# HB-UNI-Sen-PM_v2p1.net
KiCad netlist of a schematic drawn in EAGLE
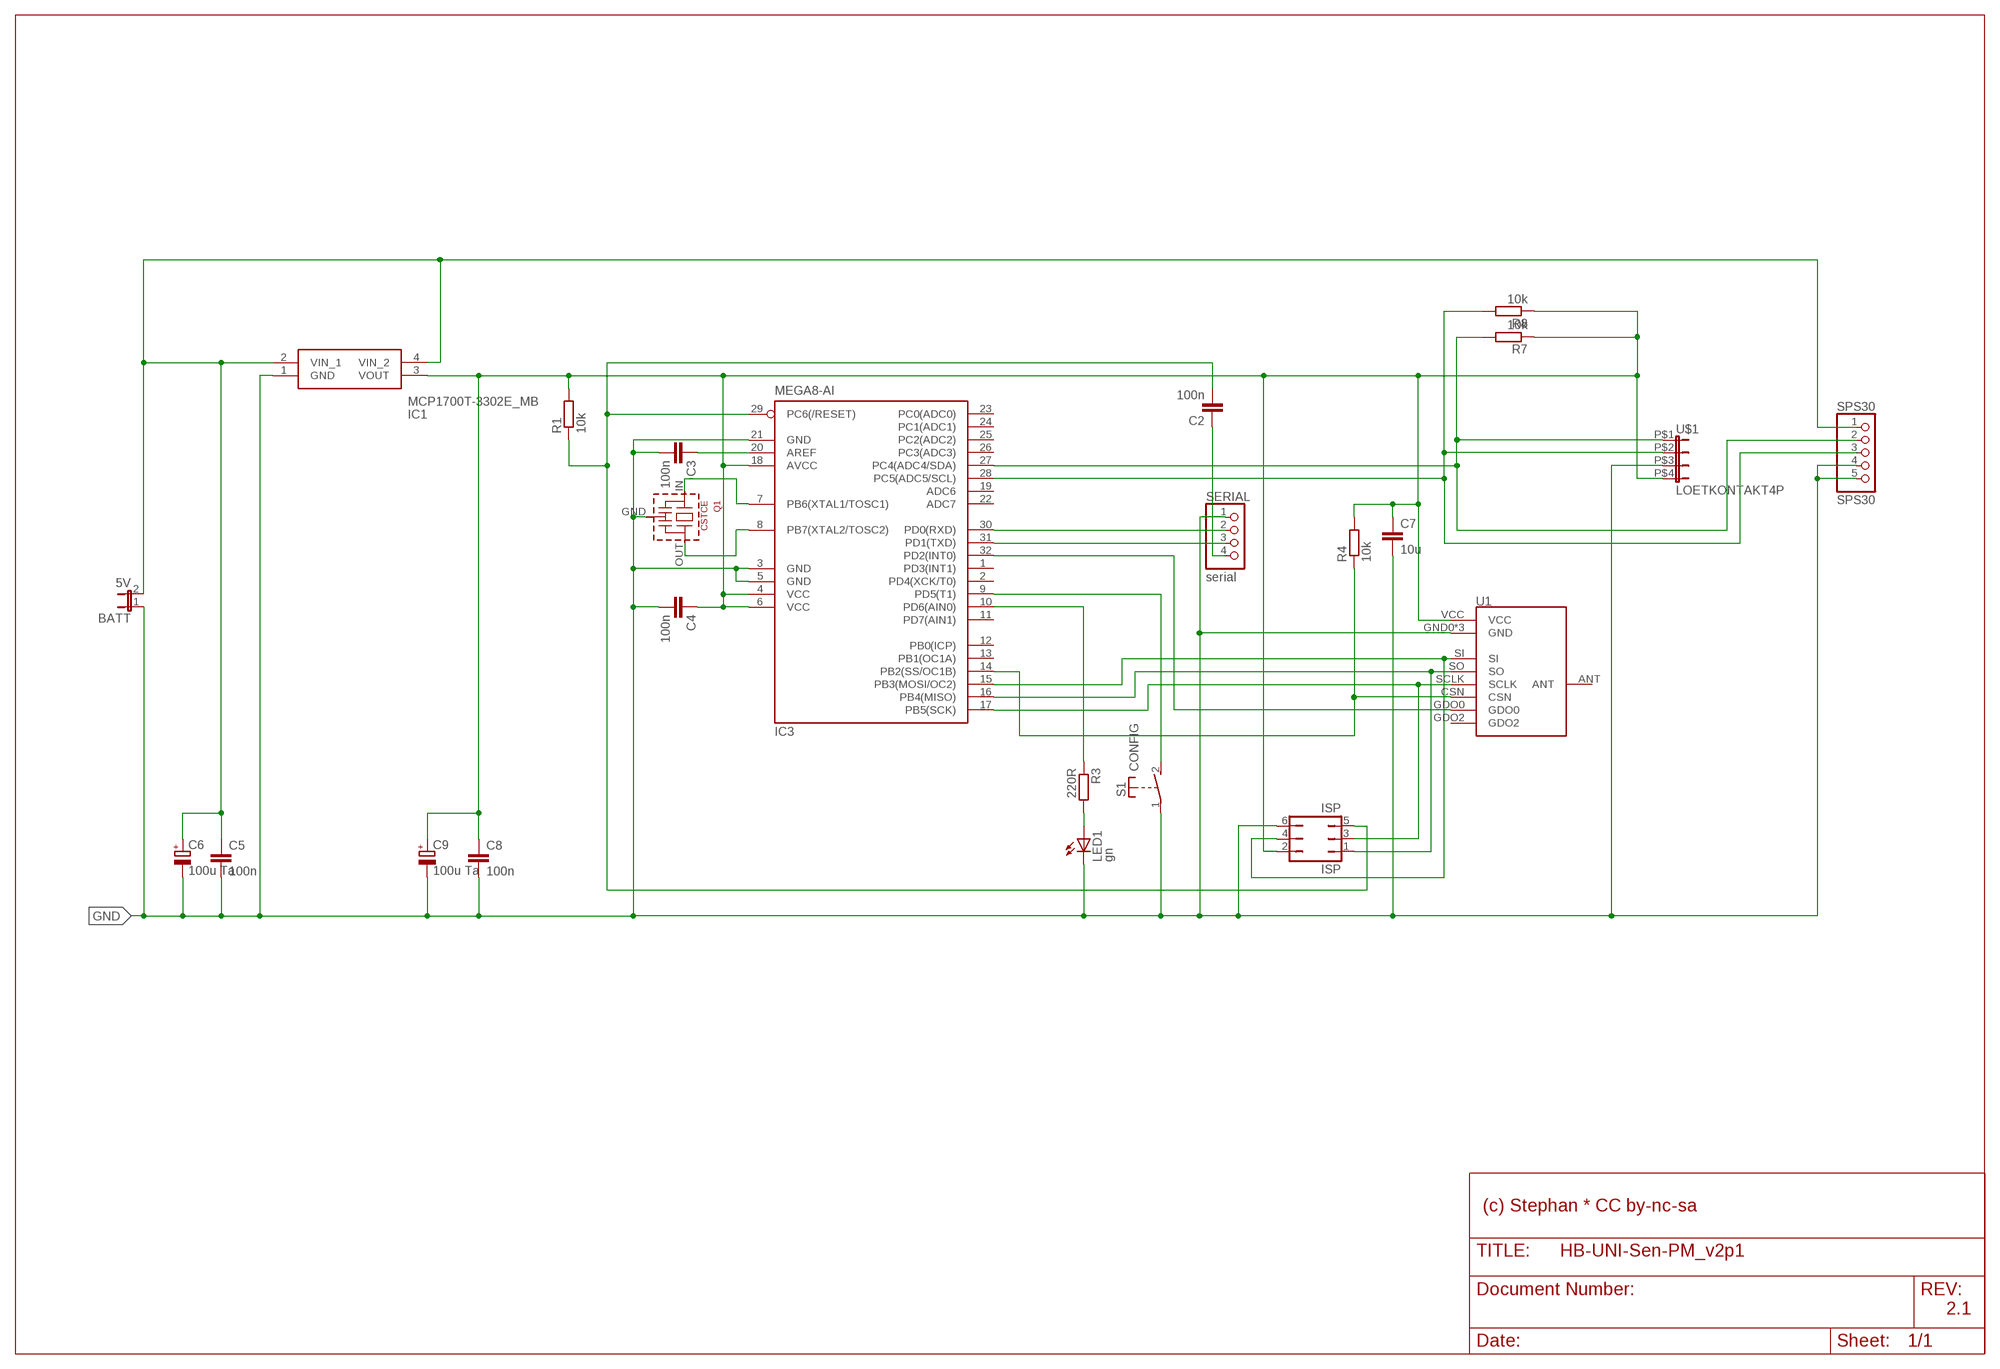
[diagram p0: schematic, sheet 1]

(export (version "E")
  (design (tool "Eeschema 10.0.6"))
  (components
    (comp (ref "BATT")
      (value "5V")
      (footprint "eagle-import:JP1")
      (libsource (lib "eagle-import") (part "JP1E"))
    )
    (comp (ref "C2")
      (value "100n")
      (footprint "eagle-import:C0805K")
      (libsource (lib "eagle-import") (part "C-EUC0805K"))
    )
    (comp (ref "C3")
      (value "100n")
      (footprint "eagle-import:C0805K")
      (libsource (lib "eagle-import") (part "C-EUC0805K"))
    )
    (comp (ref "C4")
      (value "100n")
      (footprint "eagle-import:C0805K")
      (libsource (lib "eagle-import") (part "C-EUC0805K"))
    )
    (comp (ref "C5")
      (value "100n")
      (footprint "eagle-import:C0805K")
      (libsource (lib "eagle-import") (part "C-EUC0805K"))
    )
    (comp (ref "C6")
      (value "100u Ta")
      (footprint "eagle-import:SANYO-OSCON_SMD_C6")
      (libsource (lib "eagle-import") (part "CPOL-EUSANYO_SMD_C6"))
    )
    (comp (ref "C7")
      (value "10u")
      (footprint "eagle-import:C0805K")
      (libsource (lib "eagle-import") (part "C-EUC0805K"))
    )
    (comp (ref "C8")
      (value "100n")
      (footprint "eagle-import:C0805K")
      (libsource (lib "eagle-import") (part "C-EUC0805K"))
    )
    (comp (ref "C9")
      (value "100u Ta")
      (footprint "eagle-import:SANYO-OSCON_SMD_C6")
      (libsource (lib "eagle-import") (part "CPOL-EUSANYO_SMD_C6"))
    )
    (comp (ref "IC1")
      (value "MCP1700T-3302E_MB")
      (footprint "eagle-import:MCP1700T-3302E_MB")
      (fields
        (field (name "ARROW_PART_NUMBER") "MCP1700T-3302E/MB")
        (field (name "MOUSER_PART_NUMBER") "579-MCP1700T3302E/MB")
      )
      (libsource (lib "eagle-import") (part "MCP1700T-3302E_MB"))
    )
    (comp (ref "IC3")
      (value "MEGA8-AI")
      (footprint "eagle-import:TQFP32-08")
      (fields (field (name "MPN") "ATMEGA8-16AU"))
      (libsource (lib "eagle-import") (part "MEGA8-AI"))
    )
    (comp (ref "ISP")
      (value "ISP")
      (footprint "eagle-import:JP3Q")
      (libsource (lib "eagle-import") (part "JP3Q"))
    )
    (comp (ref "LED1")
      (value "gn")
      (footprint "eagle-import:CHIPLED_0805")
      (libsource (lib "eagle-import") (part "LEDCHIPLED_0805"))
    )
    (comp (ref "Q1")
      (value "CSTCE")
      (footprint "eagle-import:CSTCE")
      (libsource (lib "eagle-import") (part "CSTCE"))
    )
    (comp (ref "R1")
      (value "10k")
      (footprint "eagle-import:R0805W")
      (libsource (lib "eagle-import") (part "R-EU_R0805W"))
    )
    (comp (ref "R3")
      (value "220R")
      (footprint "eagle-import:R0805W")
      (libsource (lib "eagle-import") (part "R-EU_R0805W"))
    )
    (comp (ref "R4")
      (value "10k")
      (footprint "eagle-import:R0805W")
      (libsource (lib "eagle-import") (part "R-EU_R0805W"))
    )
    (comp (ref "R7")
      (value "10k")
      (footprint "eagle-import:R0805W")
      (libsource (lib "eagle-import") (part "R-EU_R0805W"))
    )
    (comp (ref "R8")
      (value "10k")
      (footprint "eagle-import:R0805W")
      (libsource (lib "eagle-import") (part "R-EU_R0805W"))
    )
    (comp (ref "S1")
      (value "CONFIG")
      (footprint "eagle-import:SMDSWITCH6X4")
      (libsource (lib "eagle-import") (part "SMDSWITCH6X4"))
    )
    (comp (ref "SERIAL")
      (value "serial")
      (footprint "eagle-import:1X04")
      (libsource (lib "eagle-import") (part "PINHD-1X4"))
    )
    (comp (ref "SPS30")
      (value "SPS30")
      (footprint "eagle-import:1X05")
      (libsource (lib "eagle-import") (part "PINHD-1X5"))
    )
    (comp (ref "U$1")
      (value "LOETKONTAKT4P")
      (footprint "eagle-import:LOETKONTAKT4P")
      (libsource (lib "eagle-import") (part "LOETKONTAKT4P"))
    )
    (comp (ref "U1")
      (value "CC1101SMD")
      (footprint "eagle-import:CC1101-SMD")
      (libsource (lib "eagle-import") (part "CC1101SMD"))
    )
  )
  (nets
    (net (code "1") (name "GND") (class "Default")
      (node (ref "BATT") (pin "1") (pinfunction "1_1") (pintype "passive"))
      (node (ref "C3") (pin "2") (pinfunction "2_2") (pintype "passive"))
      (node (ref "C4") (pin "2") (pinfunction "2_2") (pintype "passive"))
      (node (ref "C5") (pin "2") (pinfunction "2_2") (pintype "passive"))
      (node (ref "C6") (pin "-") (pinfunction "-_-") (pintype "passive"))
      (node (ref "C7") (pin "2") (pinfunction "2_2") (pintype "passive"))
      (node (ref "C8") (pin "2") (pinfunction "2_2") (pintype "passive"))
      (node (ref "C9") (pin "-") (pinfunction "-_-") (pintype "passive"))
      (node (ref "IC1") (pin "1") (pinfunction "GND_1") (pintype "power_in"))
      (node (ref "IC3") (pin "21") (pinfunction "GND_21") (pintype "power_in"))
      (node (ref "IC3") (pin "3") (pinfunction "GND_3") (pintype "power_in"))
      (node (ref "IC3") (pin "5") (pinfunction "GND_5") (pintype "power_in"))
      (node (ref "ISP") (pin "6") (pinfunction "6_6") (pintype "passive"))
      (node (ref "LED1") (pin "C") (pinfunction "C_C") (pintype "passive"))
      (node (ref "Q1") (pin "GND") (pinfunction "GND_GND") (pintype "power_in"))
      (node (ref "S1") (pin "1") (pinfunction "P_1") (pintype "passive"))
      (node (ref "SERIAL") (pin "1") (pinfunction "1_1") (pintype "passive"))
      (node (ref "SPS30") (pin "4") (pinfunction "4_4") (pintype "passive"))
      (node (ref "SPS30") (pin "5") (pinfunction "5_5") (pintype "passive"))
      (node (ref "U$1") (pin "P$3") (pinfunction "3_P$3") (pintype "passive"))
      (node (ref "U1") (pin "GND0") (pinfunction "GND_GND0") (pintype "power_in"))
      (node (ref "U1") (pin "GND1") (pinfunction "GND_GND1") (pintype "power_in"))
      (node (ref "U1") (pin "GND2") (pinfunction "GND_GND2") (pintype "power_in"))
    )
    (net (code "2") (name "Net-(C2-Pad1)") (class "Default")
      (node (ref "C2") (pin "1") (pinfunction "1_1") (pintype "passive"))
      (node (ref "SERIAL") (pin "4") (pinfunction "4_4") (pintype "passive"))
    )
    (net (code "3") (name "Net-(IC1-VIN_1)") (class "Default")
      (node (ref "BATT") (pin "2") (pinfunction "2_2") (pintype "passive"))
      (node (ref "C5") (pin "1") (pinfunction "1_1") (pintype "passive"))
      (node (ref "C6") (pin "+") (pinfunction "+_+") (pintype "passive"))
      (node (ref "IC1") (pin "2") (pinfunction "VIN_1_2") (pintype "input"))
      (node (ref "IC1") (pin "4") (pinfunction "VIN_2_4") (pintype "bidirectional"))
      (node (ref "SPS30") (pin "1") (pinfunction "1_1") (pintype "passive"))
    )
    (net (code "4") (name "Net-(IC1-VOUT)") (class "Default")
      (node (ref "C4") (pin "1") (pinfunction "1_1") (pintype "passive"))
      (node (ref "C7") (pin "1") (pinfunction "1_1") (pintype "passive"))
      (node (ref "C8") (pin "1") (pinfunction "1_1") (pintype "passive"))
      (node (ref "C9") (pin "+") (pinfunction "+_+") (pintype "passive"))
      (node (ref "IC1") (pin "3") (pinfunction "VOUT_3") (pintype "output"))
      (node (ref "IC3") (pin "18") (pinfunction "AVCC_18") (pintype "power_in"))
      (node (ref "IC3") (pin "4") (pinfunction "VCC_4") (pintype "power_in"))
      (node (ref "IC3") (pin "6") (pinfunction "VCC_6") (pintype "power_in"))
      (node (ref "ISP") (pin "2") (pinfunction "2_2") (pintype "passive"))
      (node (ref "R1") (pin "2") (pinfunction "2_2") (pintype "passive"))
      (node (ref "R4") (pin "2") (pinfunction "2_2") (pintype "passive"))
      (node (ref "R7") (pin "1") (pinfunction "1_1") (pintype "passive"))
      (node (ref "R8") (pin "1") (pinfunction "1_1") (pintype "passive"))
      (node (ref "U$1") (pin "P$4") (pinfunction "4_P$4") (pintype "passive"))
      (node (ref "U1") (pin "VCC") (pinfunction "VCC_VCC") (pintype "power_in"))
    )
    (net (code "5") (name "Net-(IC3-AREF)") (class "Default")
      (node (ref "C3") (pin "1") (pinfunction "1_1") (pintype "passive"))
      (node (ref "IC3") (pin "20") (pinfunction "AREF_20") (pintype "passive"))
    )
    (net (code "6") (name "Net-(IC3-PB2(SS{slash}OC1B))") (class "Default")
      (node (ref "IC3") (pin "14") (pinfunction "PB2(SS/OC1B)_14") (pintype "bidirectional"))
      (node (ref "R4") (pin "1") (pinfunction "1_1") (pintype "passive"))
      (node (ref "U1") (pin "CSN") (pinfunction "CSN_CSN") (pintype "bidirectional"))
    )
    (net (code "7") (name "Net-(IC3-PB3(MOSI{slash}OC2))") (class "Default")
      (node (ref "IC3") (pin "15") (pinfunction "PB3(MOSI/OC2)_15") (pintype "bidirectional"))
      (node (ref "ISP") (pin "4") (pinfunction "4_4") (pintype "passive"))
      (node (ref "U1") (pin "SI") (pinfunction "SI_SI") (pintype "input"))
    )
    (net (code "8") (name "Net-(IC3-PB4(MISO))") (class "Default")
      (node (ref "IC3") (pin "16") (pinfunction "PB4(MISO)_16") (pintype "bidirectional"))
      (node (ref "ISP") (pin "1") (pinfunction "1_1") (pintype "passive"))
      (node (ref "U1") (pin "SO") (pinfunction "SO_SO") (pintype "output"))
    )
    (net (code "9") (name "Net-(IC3-PB5(SCK))") (class "Default")
      (node (ref "IC3") (pin "17") (pinfunction "PB5(SCK)_17") (pintype "bidirectional"))
      (node (ref "ISP") (pin "3") (pinfunction "3_3") (pintype "passive"))
      (node (ref "U1") (pin "SCLK") (pinfunction "SCLK_SCLK") (pintype "input"))
    )
    (net (code "10") (name "Net-(IC3-PB6(XTAL1{slash}TOSC1))") (class "Default")
      (node (ref "IC3") (pin "7") (pinfunction "PB6(XTAL1/TOSC1)_7") (pintype "bidirectional"))
      (node (ref "Q1") (pin "IN") (pinfunction "IN_IN") (pintype "input"))
    )
    (net (code "11") (name "Net-(IC3-PB7(XTAL2{slash}TOSC2))") (class "Default")
      (node (ref "IC3") (pin "8") (pinfunction "PB7(XTAL2/TOSC2)_8") (pintype "bidirectional"))
      (node (ref "Q1") (pin "OUT") (pinfunction "OUT_OUT") (pintype "output"))
    )
    (net (code "12") (name "Net-(IC3-PC4(ADC4{slash}SDA))") (class "Default")
      (node (ref "IC3") (pin "27") (pinfunction "PC4(ADC4/SDA)_27") (pintype "bidirectional"))
      (node (ref "R7") (pin "2") (pinfunction "2_2") (pintype "passive"))
      (node (ref "SPS30") (pin "2") (pinfunction "2_2") (pintype "passive"))
      (node (ref "U$1") (pin "P$1") (pinfunction "1_P$1") (pintype "passive"))
    )
    (net (code "13") (name "Net-(IC3-PC5(ADC5{slash}SCL))") (class "Default")
      (node (ref "IC3") (pin "28") (pinfunction "PC5(ADC5/SCL)_28") (pintype "bidirectional"))
      (node (ref "R8") (pin "2") (pinfunction "2_2") (pintype "passive"))
      (node (ref "SPS30") (pin "3") (pinfunction "3_3") (pintype "passive"))
      (node (ref "U$1") (pin "P$2") (pinfunction "2_P$2") (pintype "passive"))
    )
    (net (code "14") (name "Net-(IC3-PC6({slash}RESET))") (class "Default")
      (node (ref "C2") (pin "2") (pinfunction "2_2") (pintype "passive"))
      (node (ref "IC3") (pin "29") (pinfunction "PC6(/RESET)_29") (pintype "bidirectional"))
      (node (ref "ISP") (pin "5") (pinfunction "5_5") (pintype "passive"))
      (node (ref "R1") (pin "1") (pinfunction "1_1") (pintype "passive"))
    )
    (net (code "15") (name "Net-(IC3-PD0(RXD))") (class "Default")
      (node (ref "IC3") (pin "30") (pinfunction "PD0(RXD)_30") (pintype "bidirectional"))
      (node (ref "SERIAL") (pin "2") (pinfunction "2_2") (pintype "passive"))
    )
    (net (code "16") (name "Net-(IC3-PD1(TXD))") (class "Default")
      (node (ref "IC3") (pin "31") (pinfunction "PD1(TXD)_31") (pintype "bidirectional"))
      (node (ref "SERIAL") (pin "3") (pinfunction "3_3") (pintype "passive"))
    )
    (net (code "17") (name "Net-(IC3-PD2(INT0))") (class "Default")
      (node (ref "IC3") (pin "32") (pinfunction "PD2(INT0)_32") (pintype "bidirectional"))
      (node (ref "U1") (pin "GDO0") (pinfunction "GDO0_GDO0") (pintype "output"))
    )
    (net (code "18") (name "Net-(IC3-PD5(T1))") (class "Default")
      (node (ref "IC3") (pin "9") (pinfunction "PD5(T1)_9") (pintype "bidirectional"))
      (node (ref "S1") (pin "2") (pinfunction "S_2") (pintype "passive"))
    )
    (net (code "19") (name "Net-(IC3-PD6(AIN0))") (class "Default")
      (node (ref "IC3") (pin "10") (pinfunction "PD6(AIN0)_10") (pintype "bidirectional"))
      (node (ref "R3") (pin "1") (pinfunction "1_1") (pintype "passive"))
    )
    (net (code "20") (name "Net-(LED1-PadA)") (class "Default")
      (node (ref "LED1") (pin "A") (pinfunction "A_A") (pintype "passive"))
      (node (ref "R3") (pin "2") (pinfunction "2_2") (pintype "passive"))
    )
    (net (code "21") (name "unconnected-(IC3-ADC6-Pad19)") (class "Default")
      (node (ref "IC3") (pin "19") (pinfunction "ADC6_19") (pintype "bidirectional"))
    )
    (net (code "22") (name "unconnected-(IC3-ADC7-Pad22)") (class "Default")
      (node (ref "IC3") (pin "22") (pinfunction "ADC7_22") (pintype "bidirectional"))
    )
    (net (code "23") (name "unconnected-(IC3-PB0(ICP)-Pad12)") (class "Default")
      (node (ref "IC3") (pin "12") (pinfunction "PB0(ICP)_12") (pintype "bidirectional"))
    )
    (net (code "24") (name "unconnected-(IC3-PB1(OC1A)-Pad13)") (class "Default")
      (node (ref "IC3") (pin "13") (pinfunction "PB1(OC1A)_13") (pintype "bidirectional"))
    )
    (net (code "25") (name "unconnected-(IC3-PC0(ADC0)-Pad23)") (class "Default")
      (node (ref "IC3") (pin "23") (pinfunction "PC0(ADC0)_23") (pintype "bidirectional"))
    )
    (net (code "26") (name "unconnected-(IC3-PC1(ADC1)-Pad24)") (class "Default")
      (node (ref "IC3") (pin "24") (pinfunction "PC1(ADC1)_24") (pintype "bidirectional"))
    )
    (net (code "27") (name "unconnected-(IC3-PC2(ADC2)-Pad25)") (class "Default")
      (node (ref "IC3") (pin "25") (pinfunction "PC2(ADC2)_25") (pintype "bidirectional"))
    )
    (net (code "28") (name "unconnected-(IC3-PC3(ADC3)-Pad26)") (class "Default")
      (node (ref "IC3") (pin "26") (pinfunction "PC3(ADC3)_26") (pintype "bidirectional"))
    )
    (net (code "29") (name "unconnected-(IC3-PD3(INT1)-Pad1)") (class "Default")
      (node (ref "IC3") (pin "1") (pinfunction "PD3(INT1)_1") (pintype "bidirectional"))
    )
    (net (code "30") (name "unconnected-(IC3-PD4(XCK{slash}T0)-Pad2)") (class "Default")
      (node (ref "IC3") (pin "2") (pinfunction "PD4(XCK/T0)_2") (pintype "bidirectional"))
    )
    (net (code "31") (name "unconnected-(IC3-PD7(AIN1)-Pad11)") (class "Default")
      (node (ref "IC3") (pin "11") (pinfunction "PD7(AIN1)_11") (pintype "bidirectional"))
    )
    (net (code "32") (name "unconnected-(U1-PadANT)") (class "Default")
      (node (ref "U1") (pin "ANT") (pinfunction "ANT_ANT") (pintype "input"))
    )
    (net (code "33") (name "unconnected-(U1-PadGDO2)") (class "Default")
      (node (ref "U1") (pin "GDO2") (pinfunction "GDO2_GDO2") (pintype "output"))
    )
  )
)
